# 02-MCU.net
KiCad netlist of a schematic drawn in Altium Designer
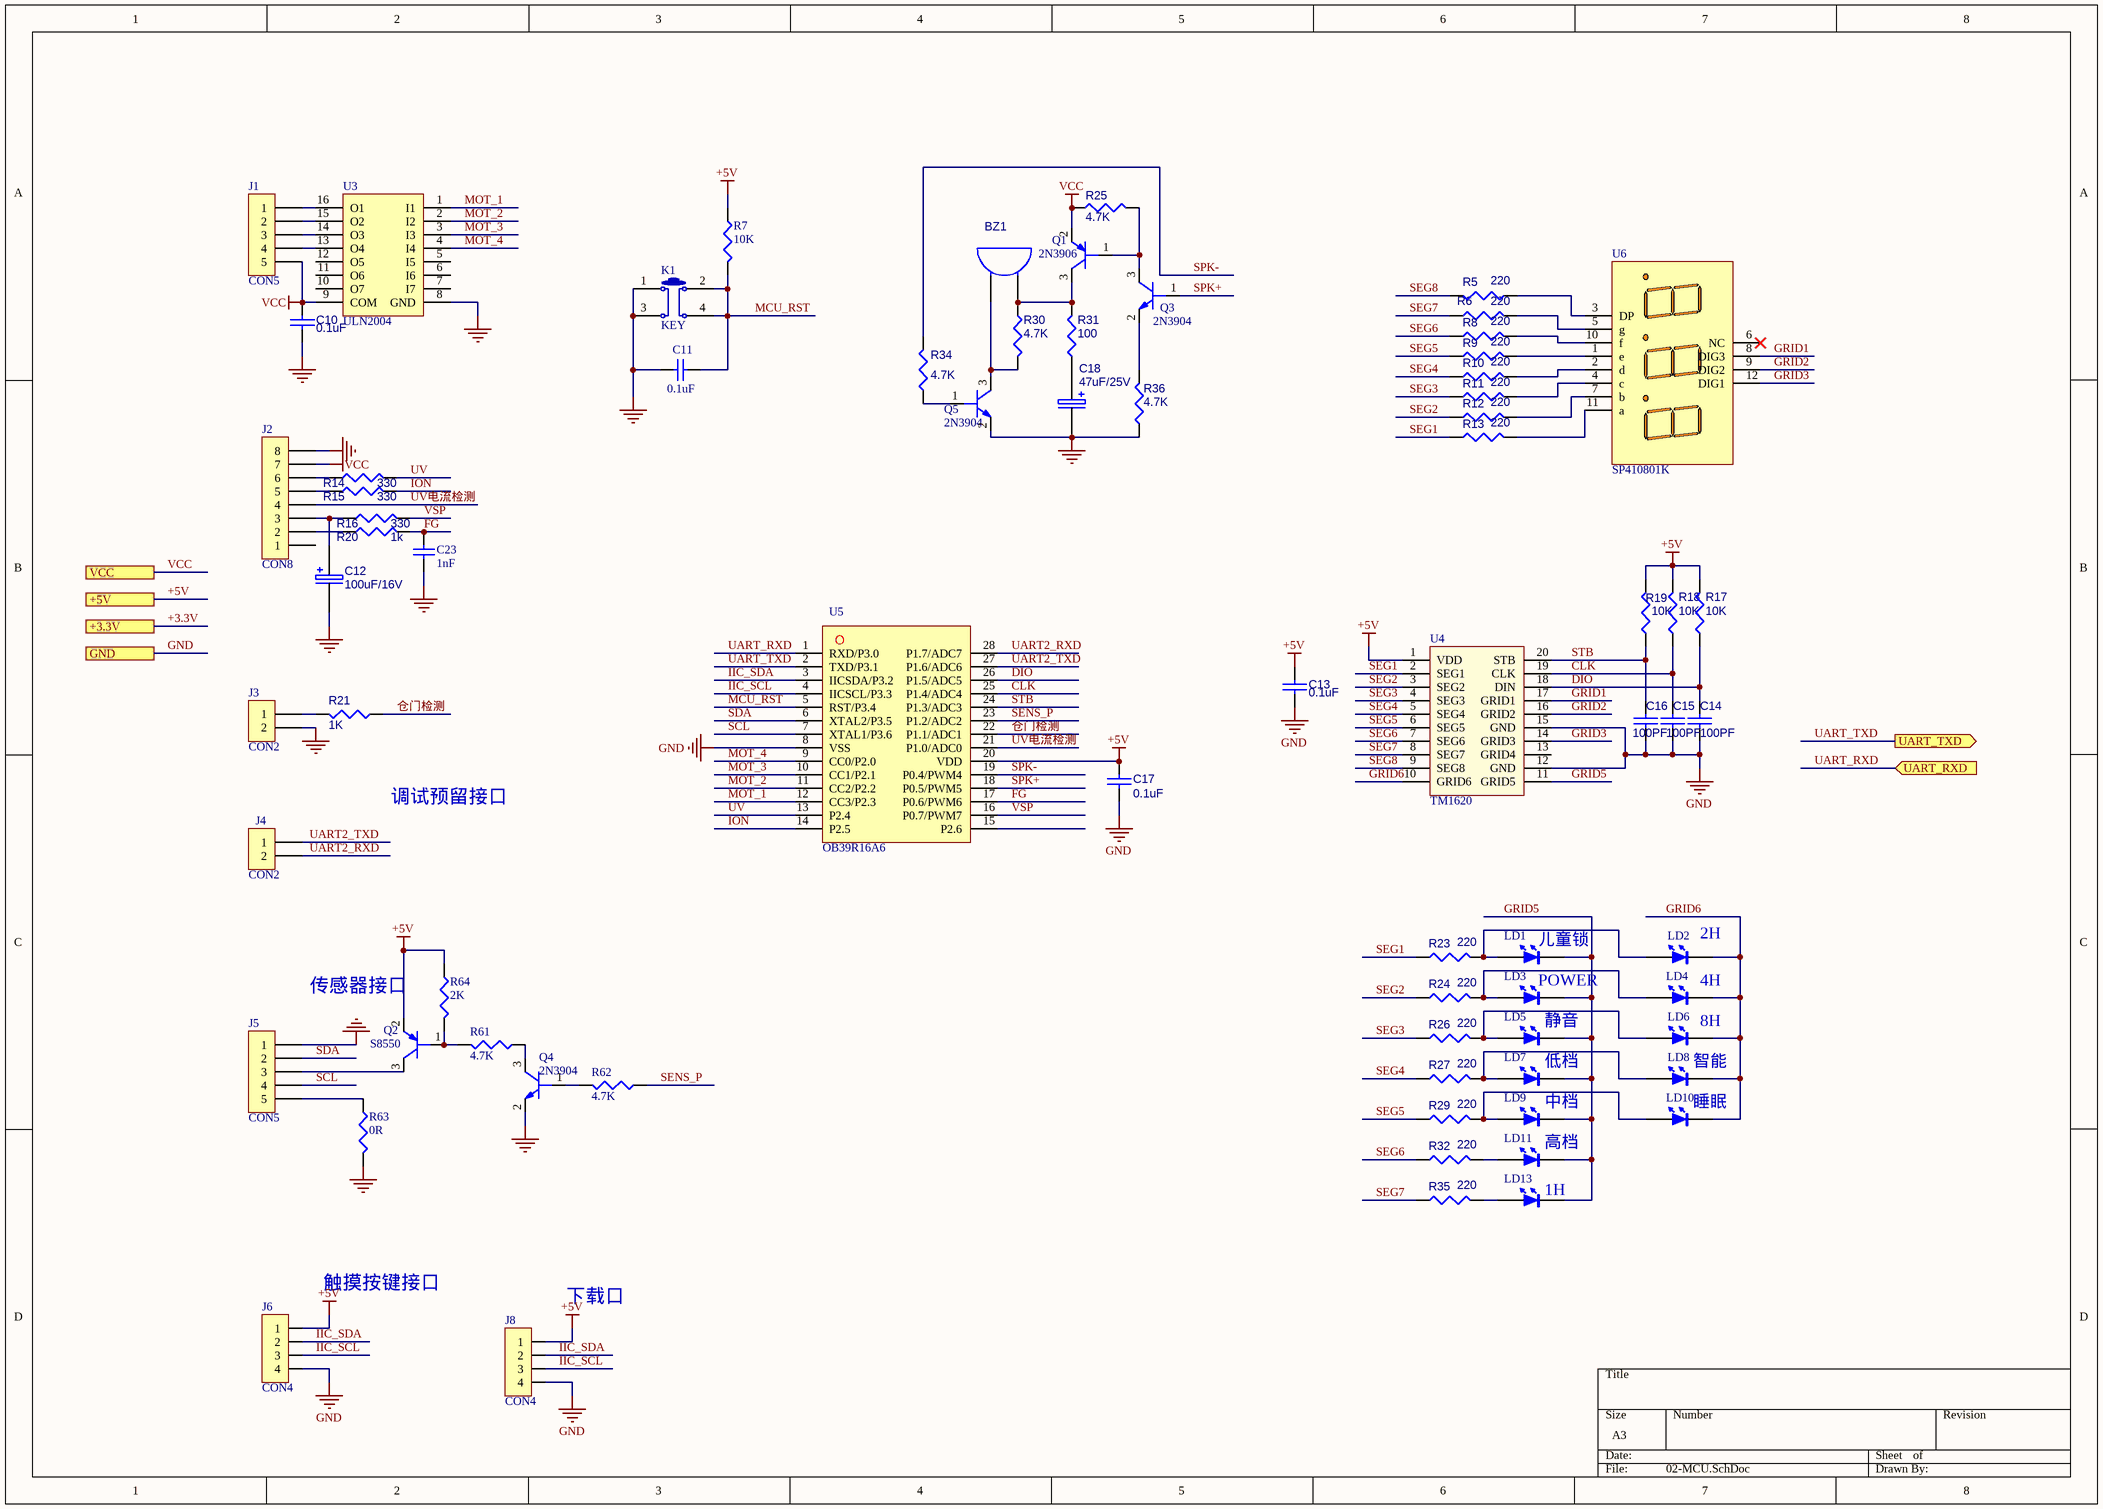
[diagram p0: 02-MCU.SchDoc]

(export (version "E")
  (design (tool "Eeschema 10.0.6"))
  (components
    (comp (ref "BZ1")
      (value "BUZZER")
      (footprint "BUZ1")
      (description "Buzzer")
      (libsource (lib "*") (part "BUZZER"))
    )
    (comp (ref "C10")
      (value "0.1uF")
      (footprint "0805_C")
      (description "CAP")
      (libsource (lib "*") (part "CAP"))
    )
    (comp (ref "C11")
      (value "0.1uF")
      (footprint "0805_C")
      (description "Capacitor")
      (fields (field (name "PUBLISHER") "Altium Limited"))
      (libsource (lib "Miscellaneous Devices") (part "Cap"))
    )
    (comp (ref "C12")
      (value "100uF/16V")
      (footprint "CE06150")
      (description "E-CAP")
      (libsource (lib "*") (part "ECAP"))
    )
    (comp (ref "C13")
      (value "0.1uF")
      (footprint "0805_C")
      (description "CAP")
      (libsource (lib "*") (part "CAP"))
    )
    (comp (ref "C14")
      (value "100PF")
      (footprint "0805_C")
      (description "CAP")
      (libsource (lib "*") (part "CAP"))
    )
    (comp (ref "C15")
      (value "100PF")
      (footprint "0805_C")
      (description "CAP")
      (libsource (lib "*") (part "CAP"))
    )
    (comp (ref "C16")
      (value "100PF")
      (footprint "0805_C")
      (description "CAP")
      (libsource (lib "*") (part "CAP"))
    )
    (comp (ref "C17")
      (value "0.1uF")
      (footprint "0805_C")
      (description "CAP")
      (libsource (lib "*") (part "CAP"))
    )
    (comp (ref "C18")
      (value "47uF/25V")
      (footprint "CE06150 - W")
      (description "E-CAP")
      (libsource (lib "*") (part "ECAP"))
    )
    (comp (ref "C23")
      (value "1nF")
      (footprint "0805_C")
      (description "Capacitor")
      (fields (field (name "PUBLISHER") "Altium Limited"))
      (libsource (lib "") (part "Cap_1"))
    )
    (comp (ref "J1")
      (value "CON5")
      (footprint "XH2.54-5PW")
      (description "Connector")
      (libsource (lib "A09F-2-KZ_20130620") (part "CON6"))
    )
    (comp (ref "J2") (value "CON8") (footprint "XH2.54-8PW") (libsource (lib "MySchlib") (part "CON8")))
    (comp (ref "J3")
      (value "CON2")
      (footprint "XH2.54-2PW")
      (description "Connector")
      (libsource (lib "A09F-2-KZ_20130620") (part "CON2"))
    )
    (comp (ref "J4")
      (value "CON2")
      (footprint "SIP2")
      (description "Connector")
      (libsource (lib "A09F-2-KZ_20130620") (part "CON2"))
    )
    (comp (ref "J5")
      (value "CON5")
      (footprint "XH2.54-5PW")
      (description "Connector")
      (libsource (lib "A09F-2-KZ_20130620") (part "CON6"))
    )
    (comp (ref "J6") (value "CON4") (footprint "XH2.54-4PW") (libsource (lib "MySchlib") (part "CON4")))
    (comp (ref "J8") (value "CON4") (footprint "SIP4") (libsource (lib "MySchlib") (part "CON4")))
    (comp (ref "K1") (value "KEY") (footprint "KEY_SMD5465") (libsource (lib "Schlib1") (part "KEY")))
    (comp (ref "LD1")
      (value "WHITE")
      (footprint "LED1")
      (description "LED")
      (libsource (lib "*") (part "LED"))
    )
    (comp (ref "LD2")
      (value "WHITE")
      (footprint "LED1")
      (description "LED")
      (libsource (lib "*") (part "LED"))
    )
    (comp (ref "LD3")
      (value "WHITE")
      (footprint "LED1")
      (description "LED")
      (libsource (lib "*") (part "LED"))
    )
    (comp (ref "LD4")
      (value "WHITE")
      (footprint "LED1")
      (description "LED")
      (libsource (lib "*") (part "LED"))
    )
    (comp (ref "LD5")
      (value "WHITE")
      (footprint "LED1")
      (description "LED")
      (libsource (lib "*") (part "LED"))
    )
    (comp (ref "LD6")
      (value "WHITE")
      (footprint "LED1")
      (description "LED")
      (libsource (lib "*") (part "LED"))
    )
    (comp (ref "LD7")
      (value "WHITE")
      (footprint "LED1")
      (description "LED")
      (libsource (lib "*") (part "LED"))
    )
    (comp (ref "LD8")
      (value "WHITE")
      (footprint "LED1")
      (description "LED")
      (libsource (lib "*") (part "LED"))
    )
    (comp (ref "LD9")
      (value "WHITE")
      (footprint "LED1")
      (description "LED")
      (libsource (lib "*") (part "LED"))
    )
    (comp (ref "LD10")
      (value "WHITE")
      (footprint "LED1")
      (description "LED")
      (libsource (lib "*") (part "LED"))
    )
    (comp (ref "LD11")
      (value "WHITE")
      (footprint "LED1")
      (description "LED")
      (libsource (lib "*") (part "LED"))
    )
    (comp (ref "LD13")
      (value "WHITE")
      (footprint "LED1")
      (description "LED")
      (libsource (lib "*") (part "LED"))
    )
    (comp (ref "Q1") (value "2N3906") (footprint "SOT23") (libsource (lib "MySchlib") (part "PNP")))
    (comp (ref "Q2") (value "S8550") (footprint "SOT23") (libsource (lib "MySchlib") (part "PNP")))
    (comp (ref "Q3") (value "2N3904") (footprint "SOT23") (libsource (lib "MySchlib") (part "NPN")))
    (comp (ref "Q4") (value "2N3904") (footprint "SOT23") (libsource (lib "MySchlib") (part "NPN")))
    (comp (ref "Q5") (value "2N3904") (footprint "SOT23") (libsource (lib "MySchlib") (part "NPN")))
    (comp (ref "R5")
      (value "220")
      (footprint "0805_R")
      (description "RESISTOR")
      (libsource (lib "*") (part "R0.25W"))
    )
    (comp (ref "R6")
      (value "220")
      (footprint "0805_R")
      (description "RESISTOR")
      (libsource (lib "*") (part "R0.25W"))
    )
    (comp (ref "R7")
      (value "10K")
      (footprint "0805_R")
      (description "Resistor")
      (fields (field (name "PUBLISHER") "Altium Limited"))
      (libsource (lib "Miscellaneous Devices") (part "Res3"))
    )
    (comp (ref "R8")
      (value "220")
      (footprint "0805_R")
      (description "RESISTOR")
      (libsource (lib "*") (part "R0.25W"))
    )
    (comp (ref "R9")
      (value "220")
      (footprint "0805_R")
      (description "RESISTOR")
      (libsource (lib "*") (part "R0.25W"))
    )
    (comp (ref "R10")
      (value "220")
      (footprint "0805_R")
      (description "RESISTOR")
      (libsource (lib "*") (part "R0.25W"))
    )
    (comp (ref "R11")
      (value "220")
      (footprint "0805_R")
      (description "RESISTOR")
      (libsource (lib "*") (part "R0.25W"))
    )
    (comp (ref "R12")
      (value "220")
      (footprint "0805_R")
      (description "RESISTOR")
      (libsource (lib "*") (part "R0.25W"))
    )
    (comp (ref "R13")
      (value "220")
      (footprint "0805_R")
      (description "RESISTOR")
      (libsource (lib "*") (part "R0.25W"))
    )
    (comp (ref "R14")
      (value "330")
      (footprint "0805_R")
      (description "RESISTOR")
      (libsource (lib "*") (part "R0.25W"))
    )
    (comp (ref "R15")
      (value "330")
      (footprint "0805_R")
      (description "RESISTOR")
      (libsource (lib "*") (part "R0.25W"))
    )
    (comp (ref "R16")
      (value "330")
      (footprint "0805_R")
      (description "RESISTOR")
      (libsource (lib "*") (part "R0.25W"))
    )
    (comp (ref "R17")
      (value "10K")
      (footprint "0805_R")
      (description "RESISTOR")
      (libsource (lib "*") (part "R0.25W"))
    )
    (comp (ref "R18")
      (value "10K")
      (footprint "0805_R")
      (description "RESISTOR")
      (libsource (lib "*") (part "R0.25W"))
    )
    (comp (ref "R19")
      (value "10K")
      (footprint "0805_R")
      (description "RESISTOR")
      (libsource (lib "*") (part "R0.25W"))
    )
    (comp (ref "R20")
      (value "1k")
      (footprint "0805_R")
      (description "RESISTOR")
      (libsource (lib "*") (part "R0.25W"))
    )
    (comp (ref "R21")
      (value "1K")
      (footprint "0805_R")
      (description "RESISTOR")
      (libsource (lib "*") (part "R0.25W"))
    )
    (comp (ref "R23")
      (value "220")
      (footprint "0805_R")
      (description "RESISTOR")
      (libsource (lib "*") (part "R0.25W"))
    )
    (comp (ref "R24")
      (value "220")
      (footprint "0805_R")
      (description "RESISTOR")
      (libsource (lib "*") (part "R0.25W"))
    )
    (comp (ref "R25")
      (value "4.7K")
      (footprint "0805_R")
      (description "RESISTOR")
      (libsource (lib "*") (part "R0.25W"))
    )
    (comp (ref "R26")
      (value "220")
      (footprint "0805_R")
      (description "RESISTOR")
      (libsource (lib "*") (part "R0.25W"))
    )
    (comp (ref "R27")
      (value "220")
      (footprint "0805_R")
      (description "RESISTOR")
      (libsource (lib "*") (part "R0.25W"))
    )
    (comp (ref "R29")
      (value "220")
      (footprint "0805_R")
      (description "RESISTOR")
      (libsource (lib "*") (part "R0.25W"))
    )
    (comp (ref "R30")
      (value "4.7K")
      (footprint "0805_R")
      (description "RESISTOR")
      (libsource (lib "*") (part "R0.25W"))
    )
    (comp (ref "R31")
      (value "100")
      (footprint "0805_R")
      (description "RESISTOR")
      (libsource (lib "*") (part "R0.25W"))
    )
    (comp (ref "R32")
      (value "220")
      (footprint "0805_R")
      (description "RESISTOR")
      (libsource (lib "*") (part "R0.25W"))
    )
    (comp (ref "R34")
      (value "4.7K")
      (footprint "0805_R")
      (description "RESISTOR")
      (libsource (lib "*") (part "R0.25W"))
    )
    (comp (ref "R35")
      (value "220")
      (footprint "0805_R")
      (description "RESISTOR")
      (libsource (lib "*") (part "R0.25W"))
    )
    (comp (ref "R36")
      (value "4.7K")
      (footprint "0805_R")
      (description "RESISTOR")
      (libsource (lib "*") (part "R0.25W"))
    )
    (comp (ref "R61") (value "4.7K") (footprint "0805_R") (libsource (lib "MySchlib") (part "RES1")))
    (comp (ref "R62") (value "4.7K") (footprint "0805_R") (libsource (lib "MySchlib") (part "RES1")))
    (comp (ref "R63") (value "0R") (footprint "0805_R") (libsource (lib "MySchlib") (part "RES1")))
    (comp (ref "R64") (value "2K") (footprint "0805_R") (libsource (lib "MySchlib") (part "RES1")))
    (comp (ref "U3") (value "ULN2004") (footprint "SOP16") (libsource (lib "MySchlib") (part "ULN2004")))
    (comp (ref "U4") (value "TM1620") (footprint "SOP20") (libsource (lib "MySchlib") (part "TM1620")))
    (comp (ref "U5")
      (value "OB39R16A6")
      (footprint "SOP28")
      (description "36 Pin AT Connector")
      (libsource (lib "A09F-2-KZ_20130620") (part "OB39R08A2"))
    )
    (comp (ref "U6")
      (value "SP410801K")
      (footprint "LED08031")
      (libsource (lib "MySchlib") (part "SP410801K"))
    )
  )
  (nets
    (net (code "1") (name "+5V") (class "Default")
      (node (ref "C13") (pin "1") (pinfunction "1_1") (pintype "passive"))
      (node (ref "C17") (pin "1") (pinfunction "1_1") (pintype "passive"))
      (node (ref "J6") (pin "1") (pinfunction "1_1") (pintype "passive"))
      (node (ref "J8") (pin "1") (pinfunction "1_1") (pintype "passive"))
      (node (ref "Q2") (pin "2") (pinfunction "EMITTER_2") (pintype "passive"))
      (node (ref "R17") (pin "1") (pinfunction "1_1") (pintype "passive"))
      (node (ref "R18") (pin "1") (pinfunction "1_1") (pintype "passive"))
      (node (ref "R19") (pin "1") (pinfunction "1_1") (pintype "passive"))
      (node (ref "R64") (pin "1") (pinfunction "1_1") (pintype "passive"))
      (node (ref "R7") (pin "2") (pinfunction "2_2") (pintype "passive"))
      (node (ref "U4") (pin "1") (pinfunction "VDD_1") (pintype "passive"))
      (node (ref "U5") (pin "20") (pinfunction "VDD_20") (pintype "passive"))
    )
    (net (code "3") (name "/CLK") (class "Default")
      (node (ref "C15") (pin "1") (pinfunction "1_1") (pintype "passive"))
      (node (ref "R18") (pin "2") (pinfunction "2_2") (pintype "passive"))
      (node (ref "U4") (pin "19") (pinfunction "CLK_19") (pintype "passive"))
      (node (ref "U5") (pin "25") (pinfunction "P1.4/ADC4_25") (pintype "passive"))
    )
    (net (code "4") (name "/DIO") (class "Default")
      (node (ref "C14") (pin "1") (pinfunction "1_1") (pintype "passive"))
      (node (ref "R17") (pin "2") (pinfunction "2_2") (pintype "passive"))
      (node (ref "U4") (pin "18") (pinfunction "DIN_18") (pintype "passive"))
      (node (ref "U5") (pin "26") (pinfunction "P1.5/ADC5_26") (pintype "passive"))
    )
    (net (code "5") (name "/FG") (class "Default")
      (node (ref "C23") (pin "2") (pinfunction "2_2") (pintype "passive"))
      (node (ref "R20") (pin "1") (pinfunction "1_1") (pintype "passive"))
      (node (ref "U5") (pin "17") (pinfunction "P0.6/PWM6_17") (pintype "passive"))
    )
    (net (code "6") (name "/GRID1") (class "Default")
      (node (ref "U4") (pin "17") (pinfunction "GRID1_17") (pintype "passive"))
      (node (ref "U6") (pin "8") (pinfunction "DIG3_8") (pintype "passive"))
    )
    (net (code "7") (name "/GRID2") (class "Default")
      (node (ref "U4") (pin "16") (pinfunction "GRID2_16") (pintype "passive"))
      (node (ref "U6") (pin "9") (pinfunction "DIG2_9") (pintype "passive"))
    )
    (net (code "8") (name "/GRID3") (class "Default")
      (node (ref "U4") (pin "14") (pinfunction "GRID3_14") (pintype "passive"))
      (node (ref "U6") (pin "12") (pinfunction "DIG1_12") (pintype "passive"))
    )
    (net (code "9") (name "/GRID5") (class "Default")
      (node (ref "LD1") (pin "K") (pinfunction "K_K") (pintype "passive"))
      (node (ref "LD11") (pin "K") (pinfunction "K_K") (pintype "passive"))
      (node (ref "LD13") (pin "K") (pinfunction "K_K") (pintype "passive"))
      (node (ref "LD3") (pin "K") (pinfunction "K_K") (pintype "passive"))
      (node (ref "LD5") (pin "K") (pinfunction "K_K") (pintype "passive"))
      (node (ref "LD7") (pin "K") (pinfunction "K_K") (pintype "passive"))
      (node (ref "LD9") (pin "K") (pinfunction "K_K") (pintype "passive"))
      (node (ref "U4") (pin "11") (pinfunction "GRID5_11") (pintype "passive"))
    )
    (net (code "10") (name "/GRID6") (class "Default")
      (node (ref "LD10") (pin "K") (pinfunction "K_K") (pintype "passive"))
      (node (ref "LD2") (pin "K") (pinfunction "K_K") (pintype "passive"))
      (node (ref "LD4") (pin "K") (pinfunction "K_K") (pintype "passive"))
      (node (ref "LD6") (pin "K") (pinfunction "K_K") (pintype "passive"))
      (node (ref "LD8") (pin "K") (pinfunction "K_K") (pintype "passive"))
      (node (ref "U4") (pin "10") (pinfunction "GRID6_10") (pintype "passive"))
    )
    (net (code "11") (name "/IIC_SCL") (class "Default")
      (node (ref "J6") (pin "3") (pinfunction "3_3") (pintype "passive"))
      (node (ref "J8") (pin "3") (pinfunction "3_3") (pintype "passive"))
      (node (ref "U5") (pin "4") (pinfunction "IICSCL/P3.3_4") (pintype "passive"))
    )
    (net (code "12") (name "/IIC_SDA") (class "Default")
      (node (ref "J6") (pin "2") (pinfunction "2_2") (pintype "passive"))
      (node (ref "J8") (pin "2") (pinfunction "2_2") (pintype "passive"))
      (node (ref "U5") (pin "3") (pinfunction "IICSDA/P3.2_3") (pintype "passive"))
    )
    (net (code "13") (name "/ION") (class "Default")
      (node (ref "R15") (pin "1") (pinfunction "1_1") (pintype "passive"))
      (node (ref "U5") (pin "14") (pinfunction "P2.5_14") (pintype "passive"))
    )
    (net (code "14") (name "/MCU_RST") (class "Default")
      (node (ref "C11") (pin "2") (pinfunction "2_2") (pintype "passive"))
      (node (ref "K1") (pin "2") (pinfunction "2_2") (pintype "passive"))
      (node (ref "K1") (pin "4") (pinfunction "4_4") (pintype "passive"))
      (node (ref "R7") (pin "1") (pinfunction "1_1") (pintype "passive"))
      (node (ref "U5") (pin "5") (pinfunction "RST/P3.4_5") (pintype "passive"))
    )
    (net (code "15") (name "/MOT_1") (class "Default")
      (node (ref "U3") (pin "1") (pinfunction "I1_1") (pintype "passive"))
      (node (ref "U5") (pin "12") (pinfunction "CC3/P2.3_12") (pintype "passive"))
    )
    (net (code "16") (name "/MOT_2") (class "Default")
      (node (ref "U3") (pin "2") (pinfunction "I2_2") (pintype "passive"))
      (node (ref "U5") (pin "11") (pinfunction "CC2/P2.2_11") (pintype "passive"))
    )
    (net (code "17") (name "/MOT_3") (class "Default")
      (node (ref "U3") (pin "3") (pinfunction "I3_3") (pintype "passive"))
      (node (ref "U5") (pin "10") (pinfunction "CC1/P2.1_10") (pintype "passive"))
    )
    (net (code "18") (name "/MOT_4") (class "Default")
      (node (ref "U3") (pin "4") (pinfunction "I4_4") (pintype "passive"))
      (node (ref "U5") (pin "9") (pinfunction "CC0/P2.0_9") (pintype "passive"))
    )
    (net (code "19") (name "/SCL") (class "Default")
      (node (ref "J5") (pin "4") (pinfunction "4_4") (pintype "passive"))
      (node (ref "U5") (pin "7") (pinfunction "XTAL1/P3.6_7") (pintype "passive"))
    )
    (net (code "20") (name "/SDA") (class "Default")
      (node (ref "J5") (pin "2") (pinfunction "2_2") (pintype "passive"))
      (node (ref "U5") (pin "6") (pinfunction "XTAL2/P3.5_6") (pintype "passive"))
    )
    (net (code "21") (name "/SEG1") (class "Default")
      (node (ref "R13") (pin "1") (pinfunction "1_1") (pintype "passive"))
      (node (ref "R23") (pin "1") (pinfunction "1_1") (pintype "passive"))
      (node (ref "U4") (pin "2") (pinfunction "SEG1_2") (pintype "passive"))
    )
    (net (code "22") (name "/SEG2") (class "Default")
      (node (ref "R12") (pin "1") (pinfunction "1_1") (pintype "passive"))
      (node (ref "R24") (pin "1") (pinfunction "1_1") (pintype "passive"))
      (node (ref "U4") (pin "3") (pinfunction "SEG2_3") (pintype "passive"))
    )
    (net (code "23") (name "/SEG3") (class "Default")
      (node (ref "R11") (pin "1") (pinfunction "1_1") (pintype "passive"))
      (node (ref "R26") (pin "1") (pinfunction "1_1") (pintype "passive"))
      (node (ref "U4") (pin "4") (pinfunction "SEG3_4") (pintype "passive"))
    )
    (net (code "24") (name "/SEG4") (class "Default")
      (node (ref "R10") (pin "1") (pinfunction "1_1") (pintype "passive"))
      (node (ref "R27") (pin "1") (pinfunction "1_1") (pintype "passive"))
      (node (ref "U4") (pin "5") (pinfunction "SEG4_5") (pintype "passive"))
    )
    (net (code "25") (name "/SEG5") (class "Default")
      (node (ref "R29") (pin "1") (pinfunction "1_1") (pintype "passive"))
      (node (ref "R9") (pin "1") (pinfunction "1_1") (pintype "passive"))
      (node (ref "U4") (pin "6") (pinfunction "SEG5_6") (pintype "passive"))
    )
    (net (code "26") (name "/SEG6") (class "Default")
      (node (ref "R32") (pin "1") (pinfunction "1_1") (pintype "passive"))
      (node (ref "R8") (pin "1") (pinfunction "1_1") (pintype "passive"))
      (node (ref "U4") (pin "7") (pinfunction "SEG6_7") (pintype "passive"))
    )
    (net (code "27") (name "/SEG7") (class "Default")
      (node (ref "R35") (pin "1") (pinfunction "1_1") (pintype "passive"))
      (node (ref "R6") (pin "1") (pinfunction "1_1") (pintype "passive"))
      (node (ref "U4") (pin "8") (pinfunction "SEG7_8") (pintype "passive"))
    )
    (net (code "28") (name "/SEG8") (class "Default")
      (node (ref "R5") (pin "1") (pinfunction "1_1") (pintype "passive"))
      (node (ref "U4") (pin "9") (pinfunction "SEG8_9") (pintype "passive"))
    )
    (net (code "29") (name "/SENS_P") (class "Default")
      (node (ref "R62") (pin "1") (pinfunction "1_1") (pintype "passive"))
      (node (ref "U5") (pin "23") (pinfunction "P1.2/ADC2_23") (pintype "passive"))
    )
    (net (code "30") (name "/SPK+") (class "Default")
      (node (ref "Q3") (pin "1") (pinfunction "BASE_1") (pintype "passive"))
      (node (ref "U5") (pin "18") (pinfunction "P0.5/PWM5_18") (pintype "passive"))
    )
    (net (code "31") (name "/SPK-") (class "Default")
      (node (ref "R34") (pin "2") (pinfunction "2_2") (pintype "passive"))
      (node (ref "U5") (pin "19") (pinfunction "P0.4/PWM4_19") (pintype "passive"))
    )
    (net (code "32") (name "/STB") (class "Default")
      (node (ref "C16") (pin "1") (pinfunction "1_1") (pintype "passive"))
      (node (ref "R19") (pin "2") (pinfunction "2_2") (pintype "passive"))
      (node (ref "U4") (pin "20") (pinfunction "STB_20") (pintype "passive"))
      (node (ref "U5") (pin "24") (pinfunction "P1.3/ADC3_24") (pintype "passive"))
    )
    (net (code "33") (name "/UART2_RXD") (class "Default")
      (node (ref "J4") (pin "2") (pinfunction "2_2") (pintype "passive"))
      (node (ref "U5") (pin "28") (pinfunction "P1.7/ADC7_28") (pintype "passive"))
    )
    (net (code "34") (name "/UART2_TXD") (class "Default")
      (node (ref "J4") (pin "1") (pinfunction "1_1") (pintype "passive"))
      (node (ref "U5") (pin "27") (pinfunction "P1.6/ADC6_27") (pintype "passive"))
    )
    (net (code "35") (name "/UART_RXD") (class "Default")
      (node (ref "U5") (pin "1") (pinfunction "RXD/P3.0_1") (pintype "passive"))
    )
    (net (code "36") (name "/UART_TXD") (class "Default")
      (node (ref "U5") (pin "2") (pinfunction "TXD/P3.1_2") (pintype "passive"))
    )
    (net (code "37") (name "/UV") (class "Default")
      (node (ref "R14") (pin "1") (pinfunction "1_1") (pintype "passive"))
      (node (ref "U5") (pin "13") (pinfunction "P2.4_13") (pintype "passive"))
    )
    (net (code "38") (name "/UV电流检测") (class "Default")
      (node (ref "J2") (pin "4") (pinfunction "4_4") (pintype "passive"))
      (node (ref "U5") (pin "21") (pinfunction "P1.0/ADC0_21") (pintype "passive"))
    )
    (net (code "39") (name "/VSP") (class "Default")
      (node (ref "R16") (pin "1") (pinfunction "1_1") (pintype "passive"))
      (node (ref "U5") (pin "16") (pinfunction "P0.7/PWM7_16") (pintype "passive"))
    )
    (net (code "40") (name "/仓门检测") (class "Default")
      (node (ref "R21") (pin "1") (pinfunction "1_1") (pintype "passive"))
      (node (ref "U5") (pin "22") (pinfunction "P1.1/ADC1_22") (pintype "passive"))
    )
    (net (code "41") (name "GND") (class "Default")
      (node (ref "C10") (pin "2") (pinfunction "2_2") (pintype "passive"))
      (node (ref "C11") (pin "1") (pinfunction "1_1") (pintype "passive"))
      (node (ref "C12") (pin "2") (pinfunction "-_2") (pintype "passive"))
      (node (ref "C13") (pin "2") (pinfunction "2_2") (pintype "passive"))
      (node (ref "C14") (pin "2") (pinfunction "2_2") (pintype "passive"))
      (node (ref "C15") (pin "2") (pinfunction "2_2") (pintype "passive"))
      (node (ref "C16") (pin "2") (pinfunction "2_2") (pintype "passive"))
      (node (ref "C17") (pin "2") (pinfunction "2_2") (pintype "passive"))
      (node (ref "C18") (pin "2") (pinfunction "-_2") (pintype "passive"))
      (node (ref "C23") (pin "1") (pinfunction "1_1") (pintype "passive"))
      (node (ref "J2") (pin "8") (pinfunction "8_8") (pintype "passive"))
      (node (ref "J3") (pin "2") (pinfunction "2_2") (pintype "passive"))
      (node (ref "J5") (pin "1") (pinfunction "1_1") (pintype "passive"))
      (node (ref "J6") (pin "4") (pinfunction "4_4") (pintype "passive"))
      (node (ref "J8") (pin "4") (pinfunction "4_4") (pintype "passive"))
      (node (ref "K1") (pin "1") (pinfunction "1_1") (pintype "passive"))
      (node (ref "K1") (pin "3") (pinfunction "3_3") (pintype "passive"))
      (node (ref "Q4") (pin "2") (pinfunction "EMITTER_2") (pintype "passive"))
      (node (ref "Q5") (pin "2") (pinfunction "EMITTER_2") (pintype "passive"))
      (node (ref "R36") (pin "1") (pinfunction "1_1") (pintype "passive"))
      (node (ref "R63") (pin "2") (pinfunction "2_2") (pintype "passive"))
      (node (ref "U3") (pin "8") (pinfunction "GND_8") (pintype "passive"))
      (node (ref "U4") (pin "12") (pinfunction "GND_12") (pintype "passive"))
      (node (ref "U4") (pin "15") (pinfunction "GND_15") (pintype "passive"))
      (node (ref "U5") (pin "8") (pinfunction "VSS_8") (pintype "passive"))
    )
    (net (code "42") (name "Net-(BZ1-A)") (class "Default")
      (node (ref "BZ1") (pin "1") (pinfunction "A_1") (pintype "passive"))
      (node (ref "Q1") (pin "3") (pinfunction "COLLECTOR_3") (pintype "passive"))
      (node (ref "R30") (pin "1") (pinfunction "1_1") (pintype "passive"))
      (node (ref "R31") (pin "2") (pinfunction "2_2") (pintype "passive"))
    )
    (net (code "43") (name "Net-(BZ1-B)") (class "Default")
      (node (ref "BZ1") (pin "2") (pinfunction "B_2") (pintype "passive"))
      (node (ref "Q5") (pin "3") (pinfunction "COLLECTOR_3") (pintype "passive"))
      (node (ref "R30") (pin "2") (pinfunction "2_2") (pintype "passive"))
    )
    (net (code "44") (name "Net-(C12-+)") (class "Default")
      (node (ref "C12") (pin "1") (pinfunction "+_1") (pintype "passive"))
      (node (ref "J2") (pin "3") (pinfunction "3_3") (pintype "passive"))
      (node (ref "R16") (pin "2") (pinfunction "2_2") (pintype "passive"))
    )
    (net (code "45") (name "Net-(C18-+)") (class "Default")
      (node (ref "C18") (pin "1") (pinfunction "+_1") (pintype "passive"))
      (node (ref "R31") (pin "1") (pinfunction "1_1") (pintype "passive"))
    )
    (net (code "46") (name "Net-(J2-Pad2)") (class "Default")
      (node (ref "J2") (pin "2") (pinfunction "2_2") (pintype "passive"))
      (node (ref "R20") (pin "2") (pinfunction "2_2") (pintype "passive"))
    )
    (net (code "47") (name "Net-(J2-Pad5)") (class "Default")
      (node (ref "J2") (pin "5") (pinfunction "5_5") (pintype "passive"))
      (node (ref "R15") (pin "2") (pinfunction "2_2") (pintype "passive"))
    )
    (net (code "48") (name "Net-(J2-Pad6)") (class "Default")
      (node (ref "J2") (pin "6") (pinfunction "6_6") (pintype "passive"))
      (node (ref "R14") (pin "2") (pinfunction "2_2") (pintype "passive"))
    )
    (net (code "49") (name "Net-(J3-Pad1)") (class "Default")
      (node (ref "J3") (pin "1") (pinfunction "1_1") (pintype "passive"))
      (node (ref "R21") (pin "2") (pinfunction "2_2") (pintype "passive"))
    )
    (net (code "50") (name "Net-(J5-Pad5)") (class "Default")
      (node (ref "J5") (pin "5") (pinfunction "5_5") (pintype "passive"))
      (node (ref "R63") (pin "1") (pinfunction "1_1") (pintype "passive"))
    )
    (net (code "51") (name "Net-(LD1-PadA)") (class "Default")
      (node (ref "LD1") (pin "A") (pinfunction "A_A") (pintype "passive"))
      (node (ref "LD2") (pin "A") (pinfunction "A_A") (pintype "passive"))
      (node (ref "R23") (pin "2") (pinfunction "2_2") (pintype "passive"))
    )
    (net (code "52") (name "Net-(LD3-PadA)") (class "Default")
      (node (ref "LD3") (pin "A") (pinfunction "A_A") (pintype "passive"))
      (node (ref "LD4") (pin "A") (pinfunction "A_A") (pintype "passive"))
      (node (ref "R24") (pin "2") (pinfunction "2_2") (pintype "passive"))
    )
    (net (code "53") (name "Net-(LD5-PadA)") (class "Default")
      (node (ref "LD5") (pin "A") (pinfunction "A_A") (pintype "passive"))
      (node (ref "LD6") (pin "A") (pinfunction "A_A") (pintype "passive"))
      (node (ref "R26") (pin "2") (pinfunction "2_2") (pintype "passive"))
    )
    (net (code "54") (name "Net-(LD7-PadA)") (class "Default")
      (node (ref "LD7") (pin "A") (pinfunction "A_A") (pintype "passive"))
      (node (ref "LD8") (pin "A") (pinfunction "A_A") (pintype "passive"))
      (node (ref "R27") (pin "2") (pinfunction "2_2") (pintype "passive"))
    )
    (net (code "55") (name "Net-(LD10-PadA)") (class "Default")
      (node (ref "LD10") (pin "A") (pinfunction "A_A") (pintype "passive"))
      (node (ref "LD9") (pin "A") (pinfunction "A_A") (pintype "passive"))
      (node (ref "R29") (pin "2") (pinfunction "2_2") (pintype "passive"))
    )
    (net (code "56") (name "Net-(LD11-PadA)") (class "Default")
      (node (ref "LD11") (pin "A") (pinfunction "A_A") (pintype "passive"))
      (node (ref "R32") (pin "2") (pinfunction "2_2") (pintype "passive"))
    )
    (net (code "57") (name "Net-(LD13-PadA)") (class "Default")
      (node (ref "LD13") (pin "A") (pinfunction "A_A") (pintype "passive"))
      (node (ref "R35") (pin "2") (pinfunction "2_2") (pintype "passive"))
    )
    (net (code "58") (name "Net-(Q1-BASE)") (class "Default")
      (node (ref "Q1") (pin "1") (pinfunction "BASE_1") (pintype "passive"))
      (node (ref "Q3") (pin "3") (pinfunction "COLLECTOR_3") (pintype "passive"))
      (node (ref "R25") (pin "2") (pinfunction "2_2") (pintype "passive"))
    )
    (net (code "59") (name "Net-(Q2-BASE)") (class "Default")
      (node (ref "Q2") (pin "1") (pinfunction "BASE_1") (pintype "passive"))
      (node (ref "R61") (pin "2") (pinfunction "2_2") (pintype "passive"))
      (node (ref "R64") (pin "2") (pinfunction "2_2") (pintype "passive"))
    )
    (net (code "60") (name "Net-(Q2-COLLECTOR)") (class "Default")
      (node (ref "J5") (pin "3") (pinfunction "3_3") (pintype "passive"))
      (node (ref "Q2") (pin "3") (pinfunction "COLLECTOR_3") (pintype "passive"))
    )
    (net (code "61") (name "Net-(Q3-EMITTER)") (class "Default")
      (node (ref "Q3") (pin "2") (pinfunction "EMITTER_2") (pintype "passive"))
      (node (ref "R36") (pin "2") (pinfunction "2_2") (pintype "passive"))
    )
    (net (code "62") (name "Net-(Q4-BASE)") (class "Default")
      (node (ref "Q4") (pin "1") (pinfunction "BASE_1") (pintype "passive"))
      (node (ref "R62") (pin "2") (pinfunction "2_2") (pintype "passive"))
    )
    (net (code "63") (name "Net-(Q4-COLLECTOR)") (class "Default")
      (node (ref "Q4") (pin "3") (pinfunction "COLLECTOR_3") (pintype "passive"))
      (node (ref "R61") (pin "1") (pinfunction "1_1") (pintype "passive"))
    )
    (net (code "64") (name "Net-(Q5-BASE)") (class "Default")
      (node (ref "Q5") (pin "1") (pinfunction "BASE_1") (pintype "passive"))
      (node (ref "R34") (pin "1") (pinfunction "1_1") (pintype "passive"))
    )
    (net (code "65") (name "Net-(U3-O1)") (class "Default")
      (node (ref "J1") (pin "1") (pinfunction "1_1") (pintype "passive"))
      (node (ref "U3") (pin "16") (pinfunction "O1_16") (pintype "passive"))
    )
    (net (code "66") (name "Net-(U3-O2)") (class "Default")
      (node (ref "J1") (pin "2") (pinfunction "2_2") (pintype "passive"))
      (node (ref "U3") (pin "15") (pinfunction "O2_15") (pintype "passive"))
    )
    (net (code "67") (name "Net-(U3-O3)") (class "Default")
      (node (ref "J1") (pin "3") (pinfunction "3_3") (pintype "passive"))
      (node (ref "U3") (pin "14") (pinfunction "O3_14") (pintype "passive"))
    )
    (net (code "68") (name "Net-(U3-O4)") (class "Default")
      (node (ref "J1") (pin "4") (pinfunction "4_4") (pintype "passive"))
      (node (ref "U3") (pin "13") (pinfunction "O4_13") (pintype "passive"))
    )
    (net (code "69") (name "Net-(U6-DP)") (class "Default")
      (node (ref "R5") (pin "2") (pinfunction "2_2") (pintype "passive"))
      (node (ref "U6") (pin "3") (pinfunction "DP_3") (pintype "passive"))
    )
    (net (code "70") (name "Net-(U6-a)") (class "Default")
      (node (ref "R13") (pin "2") (pinfunction "2_2") (pintype "passive"))
      (node (ref "U6") (pin "11") (pinfunction "a_11") (pintype "passive"))
    )
    (net (code "71") (name "Net-(U6-b)") (class "Default")
      (node (ref "R12") (pin "2") (pinfunction "2_2") (pintype "passive"))
      (node (ref "U6") (pin "7") (pinfunction "b_7") (pintype "passive"))
    )
    (net (code "72") (name "Net-(U6-c)") (class "Default")
      (node (ref "R11") (pin "2") (pinfunction "2_2") (pintype "passive"))
      (node (ref "U6") (pin "4") (pinfunction "c_4") (pintype "passive"))
    )
    (net (code "73") (name "Net-(U6-d)") (class "Default")
      (node (ref "R10") (pin "2") (pinfunction "2_2") (pintype "passive"))
      (node (ref "U6") (pin "2") (pinfunction "d_2") (pintype "passive"))
    )
    (net (code "74") (name "Net-(U6-e)") (class "Default")
      (node (ref "R9") (pin "2") (pinfunction "2_2") (pintype "passive"))
      (node (ref "U6") (pin "1") (pinfunction "e_1") (pintype "passive"))
    )
    (net (code "75") (name "Net-(U6-f)") (class "Default")
      (node (ref "R8") (pin "2") (pinfunction "2_2") (pintype "passive"))
      (node (ref "U6") (pin "10") (pinfunction "f_10") (pintype "passive"))
    )
    (net (code "76") (name "Net-(U6-g)") (class "Default")
      (node (ref "R6") (pin "2") (pinfunction "2_2") (pintype "passive"))
      (node (ref "U6") (pin "5") (pinfunction "g_5") (pintype "passive"))
    )
    (net (code "77") (name "VCC") (class "Default")
      (node (ref "C10") (pin "1") (pinfunction "1_1") (pintype "passive"))
      (node (ref "J1") (pin "5") (pinfunction "5_5") (pintype "passive"))
      (node (ref "J2") (pin "7") (pinfunction "7_7") (pintype "passive"))
      (node (ref "Q1") (pin "2") (pinfunction "EMITTER_2") (pintype "passive"))
      (node (ref "R25") (pin "1") (pinfunction "1_1") (pintype "passive"))
      (node (ref "U3") (pin "9") (pinfunction "COM_9") (pintype "passive"))
    )
    (net (code "78") (name "unconnected-(J2-Pad1)") (class "Default")
      (node (ref "J2") (pin "1") (pinfunction "1_1") (pintype "passive"))
    )
    (net (code "79") (name "unconnected-(U3-I5-Pad5)") (class "Default")
      (node (ref "U3") (pin "5") (pinfunction "I5_5") (pintype "passive"))
    )
    (net (code "80") (name "unconnected-(U3-I6-Pad6)") (class "Default")
      (node (ref "U3") (pin "6") (pinfunction "I6_6") (pintype "passive"))
    )
    (net (code "81") (name "unconnected-(U3-I7-Pad7)") (class "Default")
      (node (ref "U3") (pin "7") (pinfunction "I7_7") (pintype "passive"))
    )
    (net (code "82") (name "unconnected-(U3-O5-Pad12)") (class "Default")
      (node (ref "U3") (pin "12") (pinfunction "O5_12") (pintype "passive"))
    )
    (net (code "83") (name "unconnected-(U3-O6-Pad11)") (class "Default")
      (node (ref "U3") (pin "11") (pinfunction "O6_11") (pintype "passive"))
    )
    (net (code "84") (name "unconnected-(U3-O7-Pad10)") (class "Default")
      (node (ref "U3") (pin "10") (pinfunction "O7_10") (pintype "passive"))
    )
    (net (code "85") (name "unconnected-(U4-GRID4-Pad13)") (class "Default")
      (node (ref "U4") (pin "13") (pinfunction "GRID4_13") (pintype "passive"))
    )
    (net (code "86") (name "unconnected-(U5-P2.6-Pad15)") (class "Default")
      (node (ref "U5") (pin "15") (pinfunction "P2.6_15") (pintype "passive"))
    )
    (net (code "87") (name "unconnected-(U6-NC-Pad6)") (class "Default")
      (node (ref "U6") (pin "6") (pinfunction "NC_6") (pintype "passive+no_connect"))
    )
  )
)
